# RotaryEncoderModule_r2_0_1.net
KiCad netlist of a schematic drawn in EAGLE
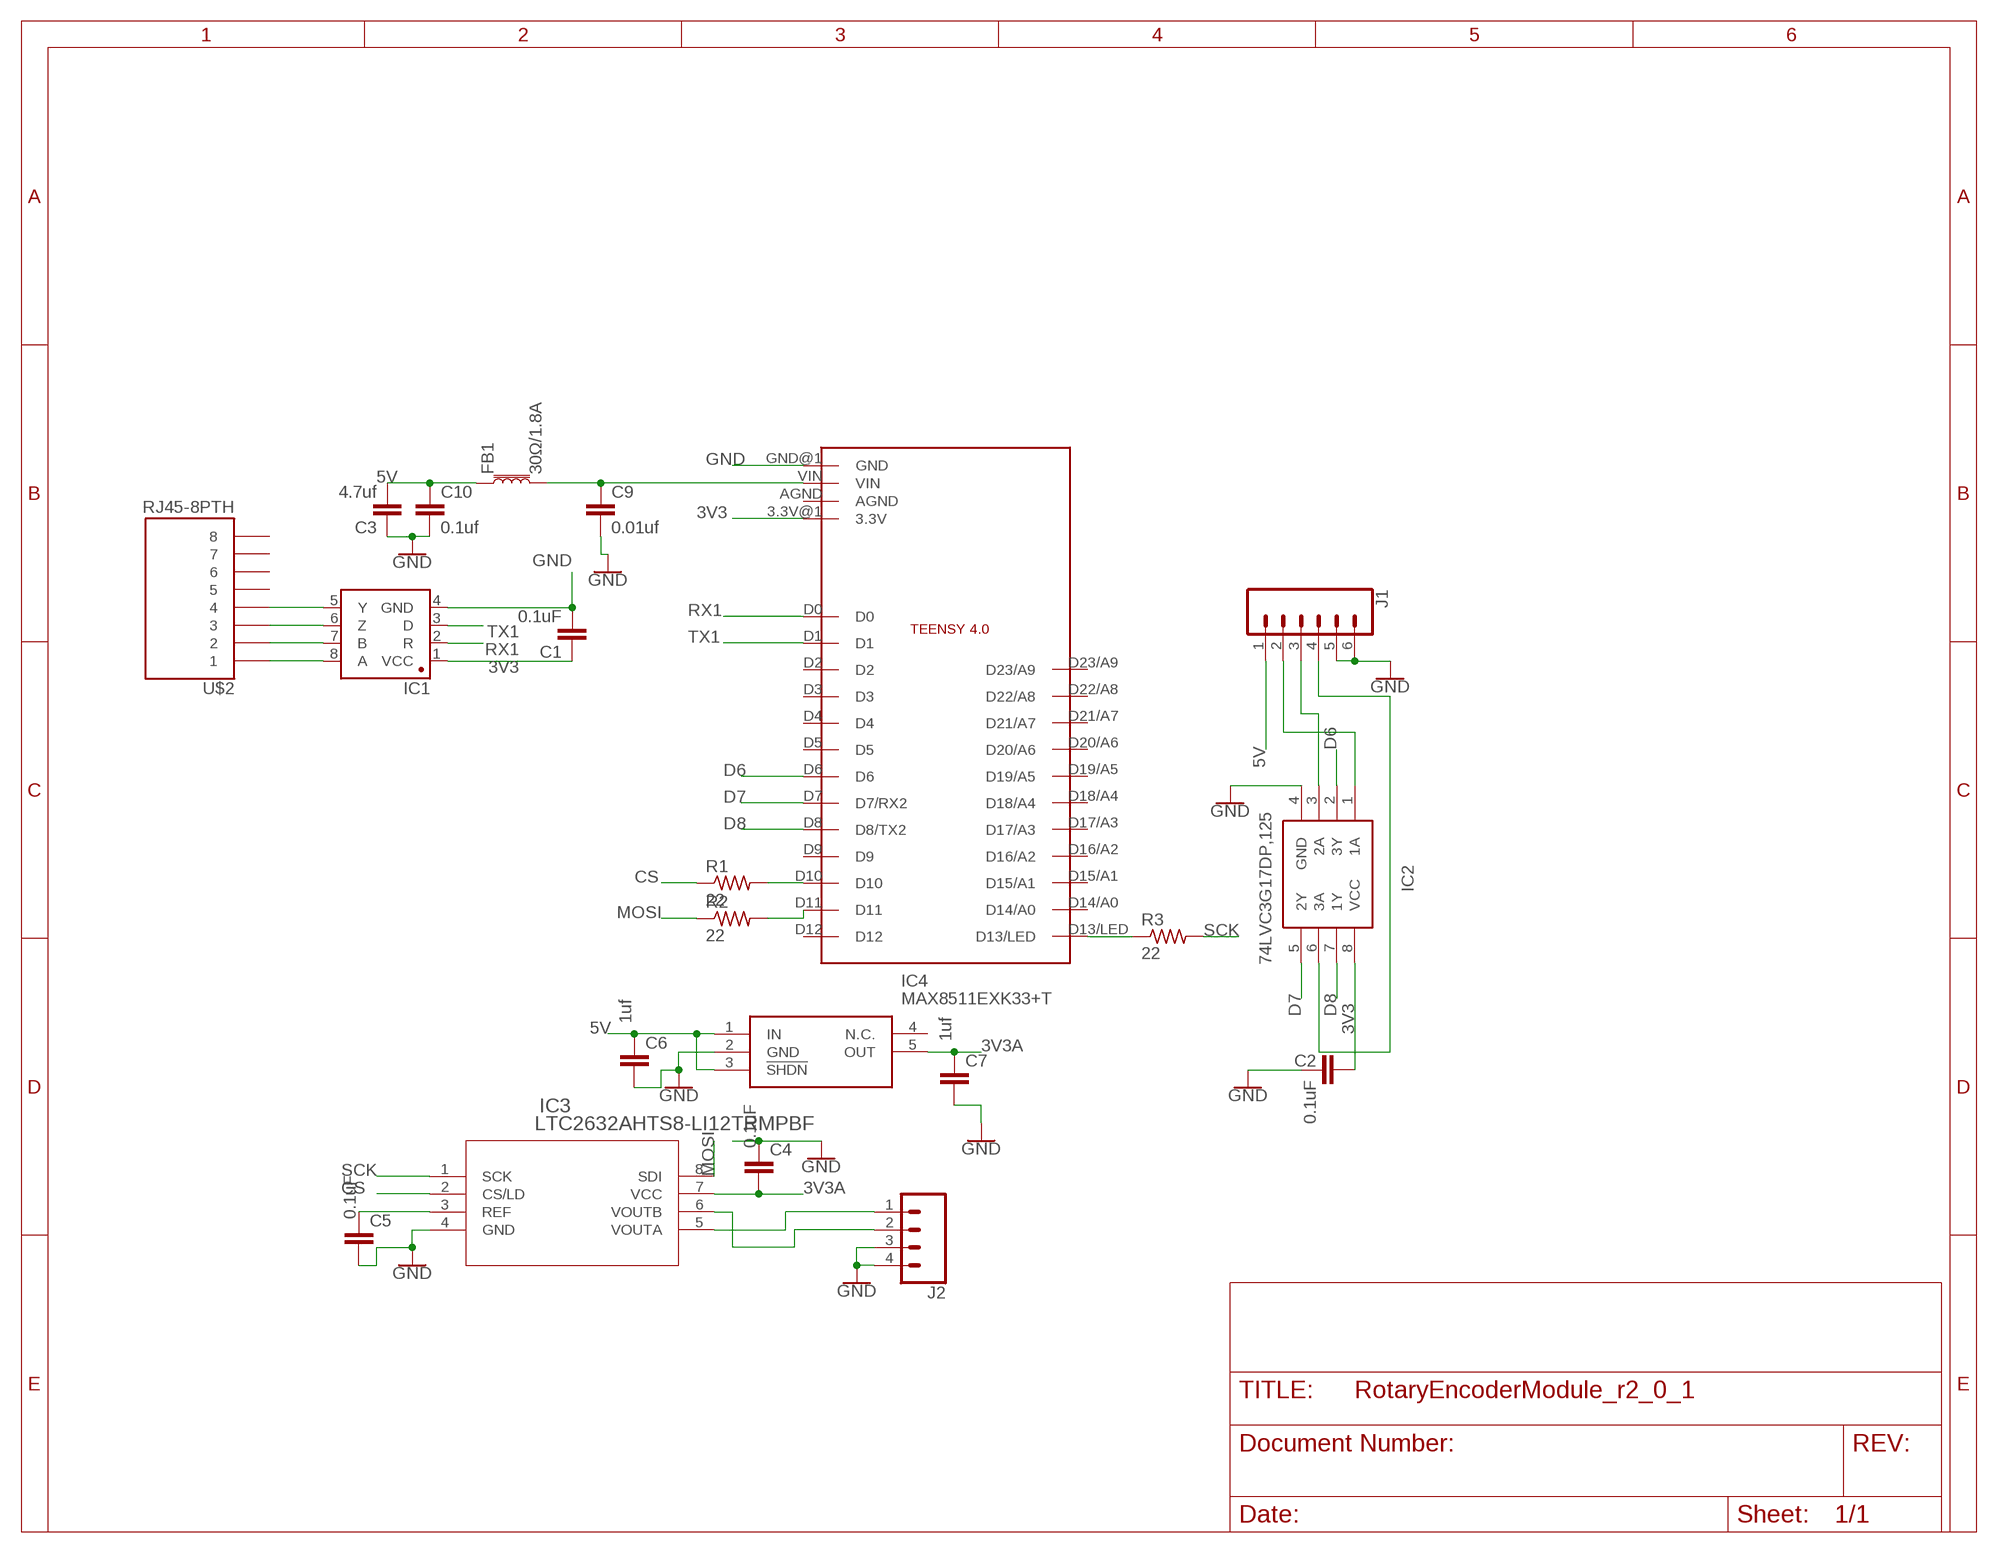
[diagram p0: schematic, sheet 1]

(export (version "E")
  (design (tool "Eeschema 10.0.6"))
  (components
    (comp (ref "C1")
      (value "0.1uF")
      (footprint "eagle-import:0805")
      (libsource (lib "eagle-import") (part "1.0UF-0805-25V-10%"))
    )
    (comp (ref "C2")
      (value "0.1uF")
      (footprint "eagle-import:0805")
      (libsource (lib "eagle-import") (part "1.0UF-0805-25V-10%"))
    )
    (comp (ref "C3")
      (value "4.7uf")
      (footprint "eagle-import:1206@2")
      (libsource (lib "eagle-import") (part "CAP1206"))
    )
    (comp (ref "C4")
      (value "0.1uF")
      (footprint "eagle-import:0805")
      (libsource (lib "eagle-import") (part "1.0UF-0805-25V-10%"))
    )
    (comp (ref "C5")
      (value "0.1uF")
      (footprint "eagle-import:0805")
      (libsource (lib "eagle-import") (part "1.0UF-0805-25V-10%"))
    )
    (comp (ref "C6")
      (value "1uf")
      (footprint "eagle-import:0805")
      (libsource (lib "eagle-import") (part "1.0UF-0805-25V-10%"))
    )
    (comp (ref "C7")
      (value "1uf")
      (footprint "eagle-import:0805")
      (libsource (lib "eagle-import") (part "1.0UF-0805-25V-10%"))
    )
    (comp (ref "C9")
      (value "0.01uf")
      (footprint "eagle-import:0805")
      (libsource (lib "eagle-import") (part "10UF-0805-10V-10%"))
    )
    (comp (ref "C10")
      (value "0.1uf")
      (footprint "eagle-import:0805")
      (libsource (lib "eagle-import") (part "10UF-0805-10V-10%"))
    )
    (comp (ref "FB1")
      (value "30Ω/1.8A")
      (footprint "eagle-import:0603")
      (libsource (lib "eagle-import") (part "FERRITE_BEAD-0603"))
    )
    (comp (ref "IC1")
      (value "SN65HVD31DR")
      (footprint "eagle-import:SO08")
      (libsource (lib "eagle-import") (part "SN65HVD31DR"))
    )
    (comp (ref "IC2")
      (value "74LVC3G17DP,125")
      (footprint "eagle-import:SOP65P400X110-8N")
      (fields (field (name "MOUSER_PART_NUMBER") "771-LVC3G17DP125"))
      (libsource (lib "eagle-import") (part "74LVC3G17DP,125"))
    )
    (comp (ref "IC3")
      (value "LTC2632AHTS8-LI12TRMPBF")
      (footprint "eagle-import:TSOT-23-8_1P625X2P9_ADI")
      (fields
        (field (name "MANUFACTURER_PART_NUMBER") "LTC2632AHTS8-LI12#TRMPBF")
        (field (name "COPYRIGHT") "Copyright (C) 2022 Ultra Librarian. All rights reserved.")
      )
      (libsource (lib "eagle-import") (part "LTC2632AHTS8-LI12TRMPBF"))
    )
    (comp (ref "IC4")
      (value "MAX8511EXK33+T")
      (footprint "eagle-import:SOT65P210X110-5N")
      (fields (field (name "MOUSER_PART_NUMBER") "700-MAX8511EXK33T"))
      (libsource (lib "eagle-import") (part "MAX8511EXK33+T"))
    )
    (comp (ref "J1")
      (value "CONN_063.5MM-6")
      (footprint "eagle-import:SCREWTERMINAL-3.5MM-6")
      (libsource (lib "eagle-import") (part "CONN_063.5MM-6"))
    )
    (comp (ref "J2")
      (value "CONN_04SCREW_LOCK")
      (footprint "eagle-import:SCREWTERMINAL-3.5MM-4_LOCK")
      (libsource (lib "eagle-import") (part "CONN_04SCREW_LOCK"))
    )
    (comp (ref "MC1")
      (value "TEENSY4.0_SIMPLE_NO_VUSB")
      (footprint "eagle-import:TEENSY4.0_SIMPLE_NO_VUSB")
      (libsource (lib "eagle-import") (part "TEENSY4.0_SIMPLE_NO_VUSB"))
    )
    (comp (ref "R1")
      (value "22")
      (footprint "eagle-import:R0805")
      (libsource (lib "eagle-import") (part "R-US_R0805"))
    )
    (comp (ref "R2")
      (value "22")
      (footprint "eagle-import:R0805")
      (libsource (lib "eagle-import") (part "R-US_R0805"))
    )
    (comp (ref "R3")
      (value "22")
      (footprint "eagle-import:R0805")
      (libsource (lib "eagle-import") (part "R-US_R0805"))
    )
    (comp (ref "U$2")
      (value "RJ45-8PTH")
      (footprint "eagle-import:RJ45-8")
      (libsource (lib "eagle-import") (part "RJ45-8PTH"))
    )
  )
  (nets
    (net (code "1") (name "/3V3") (class "Default")
      (node (ref "C1") (pin "1") (pinfunction "1_1") (pintype "passive"))
      (node (ref "C2") (pin "1") (pinfunction "1_1") (pintype "passive"))
      (node (ref "IC1") (pin "1") (pinfunction "VCC_1") (pintype "bidirectional"))
      (node (ref "IC2") (pin "8") (pinfunction "VCC_8") (pintype "bidirectional"))
      (node (ref "MC1") (pin "3.3V@1") (pinfunction "3.3V_3.3V@1") (pintype "bidirectional"))
    )
    (net (code "2") (name "/3V3A") (class "Default")
      (node (ref "C4") (pin "2") (pinfunction "2_2") (pintype "passive"))
      (node (ref "C7") (pin "1") (pinfunction "1_1") (pintype "passive"))
      (node (ref "IC3") (pin "7") (pinfunction "VCC_7") (pintype "power_in"))
      (node (ref "IC4") (pin "5") (pinfunction "OUT_5") (pintype "bidirectional"))
    )
    (net (code "3") (name "/5V") (class "Default")
      (node (ref "C10") (pin "1") (pinfunction "1_1") (pintype "passive"))
      (node (ref "C3") (pin "2") (pinfunction "2_2") (pintype "passive"))
      (node (ref "C6") (pin "1") (pinfunction "1_1") (pintype "passive"))
      (node (ref "FB1") (pin "1") (pinfunction "1_1") (pintype "passive"))
      (node (ref "IC4") (pin "1") (pinfunction "IN_1") (pintype "bidirectional"))
      (node (ref "IC4") (pin "3") (pinfunction "~{SHDN}_3") (pintype "bidirectional"))
      (node (ref "J1") (pin "1") (pinfunction "1_1") (pintype "passive"))
    )
    (net (code "4") (name "/CS") (class "Default")
      (node (ref "IC3") (pin "2") (pinfunction "CS/LD_2") (pintype "passive"))
      (node (ref "R1") (pin "1") (pinfunction "1_1") (pintype "passive"))
    )
    (net (code "5") (name "/D6") (class "Default")
      (node (ref "IC2") (pin "2") (pinfunction "3Y_2") (pintype "bidirectional"))
      (node (ref "MC1") (pin "D6") (pinfunction "D6_D6") (pintype "bidirectional"))
    )
    (net (code "6") (name "/D7") (class "Default")
      (node (ref "IC2") (pin "5") (pinfunction "2Y_5") (pintype "bidirectional"))
      (node (ref "MC1") (pin "D7") (pinfunction "D7/RX2_D7") (pintype "bidirectional"))
    )
    (net (code "7") (name "/D8") (class "Default")
      (node (ref "IC2") (pin "7") (pinfunction "1Y_7") (pintype "bidirectional"))
      (node (ref "MC1") (pin "D8") (pinfunction "D8/TX2_D8") (pintype "bidirectional"))
    )
    (net (code "8") (name "/MOSI") (class "Default")
      (node (ref "IC3") (pin "8") (pinfunction "SDI_8") (pintype "passive"))
      (node (ref "R2") (pin "1") (pinfunction "1_1") (pintype "passive"))
    )
    (net (code "9") (name "/RX1") (class "Default")
      (node (ref "IC1") (pin "2") (pinfunction "R_2") (pintype "bidirectional"))
      (node (ref "MC1") (pin "D0") (pinfunction "D0_D0") (pintype "bidirectional"))
    )
    (net (code "10") (name "/SCK") (class "Default")
      (node (ref "IC3") (pin "1") (pinfunction "SCK_1") (pintype "passive"))
      (node (ref "R3") (pin "2") (pinfunction "2_2") (pintype "passive"))
    )
    (net (code "11") (name "/TX1") (class "Default")
      (node (ref "IC1") (pin "3") (pinfunction "D_3") (pintype "bidirectional"))
      (node (ref "MC1") (pin "D1") (pinfunction "D1_D1") (pintype "bidirectional"))
    )
    (net (code "12") (name "GND") (class "Default")
      (node (ref "C1") (pin "2") (pinfunction "2_2") (pintype "passive"))
      (node (ref "C10") (pin "2") (pinfunction "2_2") (pintype "passive"))
      (node (ref "C2") (pin "2") (pinfunction "2_2") (pintype "passive"))
      (node (ref "C3") (pin "1") (pinfunction "1_1") (pintype "passive"))
      (node (ref "C4") (pin "1") (pinfunction "1_1") (pintype "passive"))
      (node (ref "C5") (pin "2") (pinfunction "2_2") (pintype "passive"))
      (node (ref "C6") (pin "2") (pinfunction "2_2") (pintype "passive"))
      (node (ref "C7") (pin "2") (pinfunction "2_2") (pintype "passive"))
      (node (ref "C9") (pin "2") (pinfunction "2_2") (pintype "passive"))
      (node (ref "IC1") (pin "4") (pinfunction "GND_4") (pintype "bidirectional"))
      (node (ref "IC2") (pin "4") (pinfunction "GND_4") (pintype "bidirectional"))
      (node (ref "IC3") (pin "4") (pinfunction "GND_4") (pintype "passive"))
      (node (ref "IC4") (pin "2") (pinfunction "GND_2") (pintype "bidirectional"))
      (node (ref "J1") (pin "5") (pinfunction "5_5") (pintype "passive"))
      (node (ref "J1") (pin "6") (pinfunction "6_6") (pintype "passive"))
      (node (ref "J2") (pin "3") (pinfunction "3_3") (pintype "passive"))
      (node (ref "J2") (pin "4") (pinfunction "4_4") (pintype "passive"))
      (node (ref "MC1") (pin "GND@1") (pinfunction "GND_GND@1") (pintype "bidirectional"))
    )
    (net (code "13") (name "Net-(C9-Pad1)") (class "Default")
      (node (ref "C9") (pin "1") (pinfunction "1_1") (pintype "passive"))
      (node (ref "FB1") (pin "2") (pinfunction "2_2") (pintype "passive"))
      (node (ref "MC1") (pin "VIN") (pinfunction "VIN_VIN") (pintype "bidirectional"))
    )
    (net (code "14") (name "Net-(IC1-A)") (class "Default")
      (node (ref "IC1") (pin "8") (pinfunction "A_8") (pintype "bidirectional"))
      (node (ref "U$2") (pin "1") (pinfunction "1_1") (pintype "bidirectional"))
    )
    (net (code "15") (name "Net-(IC1-B)") (class "Default")
      (node (ref "IC1") (pin "7") (pinfunction "B_7") (pintype "bidirectional"))
      (node (ref "U$2") (pin "2") (pinfunction "2_2") (pintype "bidirectional"))
    )
    (net (code "16") (name "Net-(IC1-Y)") (class "Default")
      (node (ref "IC1") (pin "5") (pinfunction "Y_5") (pintype "bidirectional"))
      (node (ref "U$2") (pin "4") (pinfunction "4_4") (pintype "bidirectional"))
    )
    (net (code "17") (name "Net-(IC1-Z)") (class "Default")
      (node (ref "IC1") (pin "6") (pinfunction "Z_6") (pintype "bidirectional"))
      (node (ref "U$2") (pin "3") (pinfunction "3_3") (pintype "bidirectional"))
    )
    (net (code "18") (name "Net-(IC2-1A)") (class "Default")
      (node (ref "IC2") (pin "1") (pinfunction "1A_1") (pintype "bidirectional"))
      (node (ref "J1") (pin "2") (pinfunction "2_2") (pintype "passive"))
    )
    (net (code "19") (name "Net-(IC2-2A)") (class "Default")
      (node (ref "IC2") (pin "3") (pinfunction "2A_3") (pintype "bidirectional"))
      (node (ref "J1") (pin "3") (pinfunction "3_3") (pintype "passive"))
    )
    (net (code "20") (name "Net-(IC2-3A)") (class "Default")
      (node (ref "IC2") (pin "6") (pinfunction "3A_6") (pintype "bidirectional"))
      (node (ref "J1") (pin "4") (pinfunction "4_4") (pintype "passive"))
    )
    (net (code "21") (name "Net-(IC3-REF)") (class "Default")
      (node (ref "C5") (pin "1") (pinfunction "1_1") (pintype "passive"))
      (node (ref "IC3") (pin "3") (pinfunction "REF_3") (pintype "passive"))
    )
    (net (code "22") (name "Net-(IC3-VOUTA)") (class "Default")
      (node (ref "IC3") (pin "5") (pinfunction "VOUTA_5") (pintype "output"))
      (node (ref "J2") (pin "1") (pinfunction "1_1") (pintype "passive"))
    )
    (net (code "23") (name "Net-(IC3-VOUTB)") (class "Default")
      (node (ref "IC3") (pin "6") (pinfunction "VOUTB_6") (pintype "output"))
      (node (ref "J2") (pin "2") (pinfunction "2_2") (pintype "passive"))
    )
    (net (code "24") (name "Net-(MC1-PadD10)") (class "Default")
      (node (ref "MC1") (pin "D10") (pinfunction "D10_D10") (pintype "bidirectional"))
      (node (ref "R1") (pin "2") (pinfunction "2_2") (pintype "passive"))
    )
    (net (code "25") (name "Net-(MC1-PadD11)") (class "Default")
      (node (ref "MC1") (pin "D11") (pinfunction "D11_D11") (pintype "bidirectional"))
      (node (ref "R2") (pin "2") (pinfunction "2_2") (pintype "passive"))
    )
    (net (code "26") (name "Net-(MC1-PadD13{slash}LED)") (class "Default")
      (node (ref "MC1") (pin "D13/LED") (pinfunction "D13/LED_D13/LED") (pintype "bidirectional"))
      (node (ref "R3") (pin "1") (pinfunction "1_1") (pintype "passive"))
    )
    (net (code "27") (name "unconnected-(IC4-N.C.-Pad4)") (class "Default")
      (node (ref "IC4") (pin "4") (pinfunction "N.C._4") (pintype "no_connect"))
    )
    (net (code "28") (name "unconnected-(MC1-PadAGND)") (class "Default")
      (node (ref "MC1") (pin "AGND") (pinfunction "AGND_AGND") (pintype "bidirectional"))
    )
    (net (code "29") (name "unconnected-(MC1-PadD2)") (class "Default")
      (node (ref "MC1") (pin "D2") (pinfunction "D2_D2") (pintype "bidirectional"))
    )
    (net (code "30") (name "unconnected-(MC1-PadD3)") (class "Default")
      (node (ref "MC1") (pin "D3") (pinfunction "D3_D3") (pintype "bidirectional"))
    )
    (net (code "31") (name "unconnected-(MC1-PadD4)") (class "Default")
      (node (ref "MC1") (pin "D4") (pinfunction "D4_D4") (pintype "bidirectional"))
    )
    (net (code "32") (name "unconnected-(MC1-PadD5)") (class "Default")
      (node (ref "MC1") (pin "D5") (pinfunction "D5_D5") (pintype "bidirectional"))
    )
    (net (code "33") (name "unconnected-(MC1-PadD9)") (class "Default")
      (node (ref "MC1") (pin "D9") (pinfunction "D9_D9") (pintype "bidirectional"))
    )
    (net (code "34") (name "unconnected-(MC1-PadD12)") (class "Default")
      (node (ref "MC1") (pin "D12") (pinfunction "D12_D12") (pintype "bidirectional"))
    )
    (net (code "35") (name "unconnected-(MC1-PadD14{slash}A0)") (class "Default")
      (node (ref "MC1") (pin "D14/A0") (pinfunction "D14/A0_D14/A0") (pintype "bidirectional"))
    )
    (net (code "36") (name "unconnected-(MC1-PadD15{slash}A1)") (class "Default")
      (node (ref "MC1") (pin "D15/A1") (pinfunction "D15/A1_D15/A1") (pintype "bidirectional"))
    )
    (net (code "37") (name "unconnected-(MC1-PadD16{slash}A2)") (class "Default")
      (node (ref "MC1") (pin "D16/A2") (pinfunction "D16/A2_D16/A2") (pintype "bidirectional"))
    )
    (net (code "38") (name "unconnected-(MC1-PadD17{slash}A3)") (class "Default")
      (node (ref "MC1") (pin "D17/A3") (pinfunction "D17/A3_D17/A3") (pintype "bidirectional"))
    )
    (net (code "39") (name "unconnected-(MC1-PadD18{slash}A4)") (class "Default")
      (node (ref "MC1") (pin "D18/A4") (pinfunction "D18/A4_D18/A4") (pintype "bidirectional"))
    )
    (net (code "40") (name "unconnected-(MC1-PadD19{slash}A5)") (class "Default")
      (node (ref "MC1") (pin "D19/A5") (pinfunction "D19/A5_D19/A5") (pintype "bidirectional"))
    )
    (net (code "41") (name "unconnected-(MC1-PadD20{slash}A6)") (class "Default")
      (node (ref "MC1") (pin "D20/A6") (pinfunction "D20/A6_D20/A6") (pintype "bidirectional"))
    )
    (net (code "42") (name "unconnected-(MC1-PadD21{slash}A7)") (class "Default")
      (node (ref "MC1") (pin "D21/A7") (pinfunction "D21/A7_D21/A7") (pintype "bidirectional"))
    )
    (net (code "43") (name "unconnected-(MC1-PadD22{slash}A8)") (class "Default")
      (node (ref "MC1") (pin "D22/A8") (pinfunction "D22/A8_D22/A8") (pintype "bidirectional"))
    )
    (net (code "44") (name "unconnected-(MC1-PadD23{slash}A9)") (class "Default")
      (node (ref "MC1") (pin "D23/A9") (pinfunction "D23/A9_D23/A9") (pintype "bidirectional"))
    )
    (net (code "45") (name "unconnected-(U$2-Pad5)") (class "Default")
      (node (ref "U$2") (pin "5") (pinfunction "5_5") (pintype "bidirectional"))
    )
    (net (code "46") (name "unconnected-(U$2-Pad6)") (class "Default")
      (node (ref "U$2") (pin "6") (pinfunction "6_6") (pintype "bidirectional"))
    )
    (net (code "47") (name "unconnected-(U$2-Pad7)") (class "Default")
      (node (ref "U$2") (pin "7") (pinfunction "7_7") (pintype "bidirectional"))
    )
    (net (code "48") (name "unconnected-(U$2-Pad8)") (class "Default")
      (node (ref "U$2") (pin "8") (pinfunction "8_8") (pintype "bidirectional"))
    )
  )
)
